# ATTiny13_TestBoard.net
KiCad netlist of a schematic drawn in EAGLE
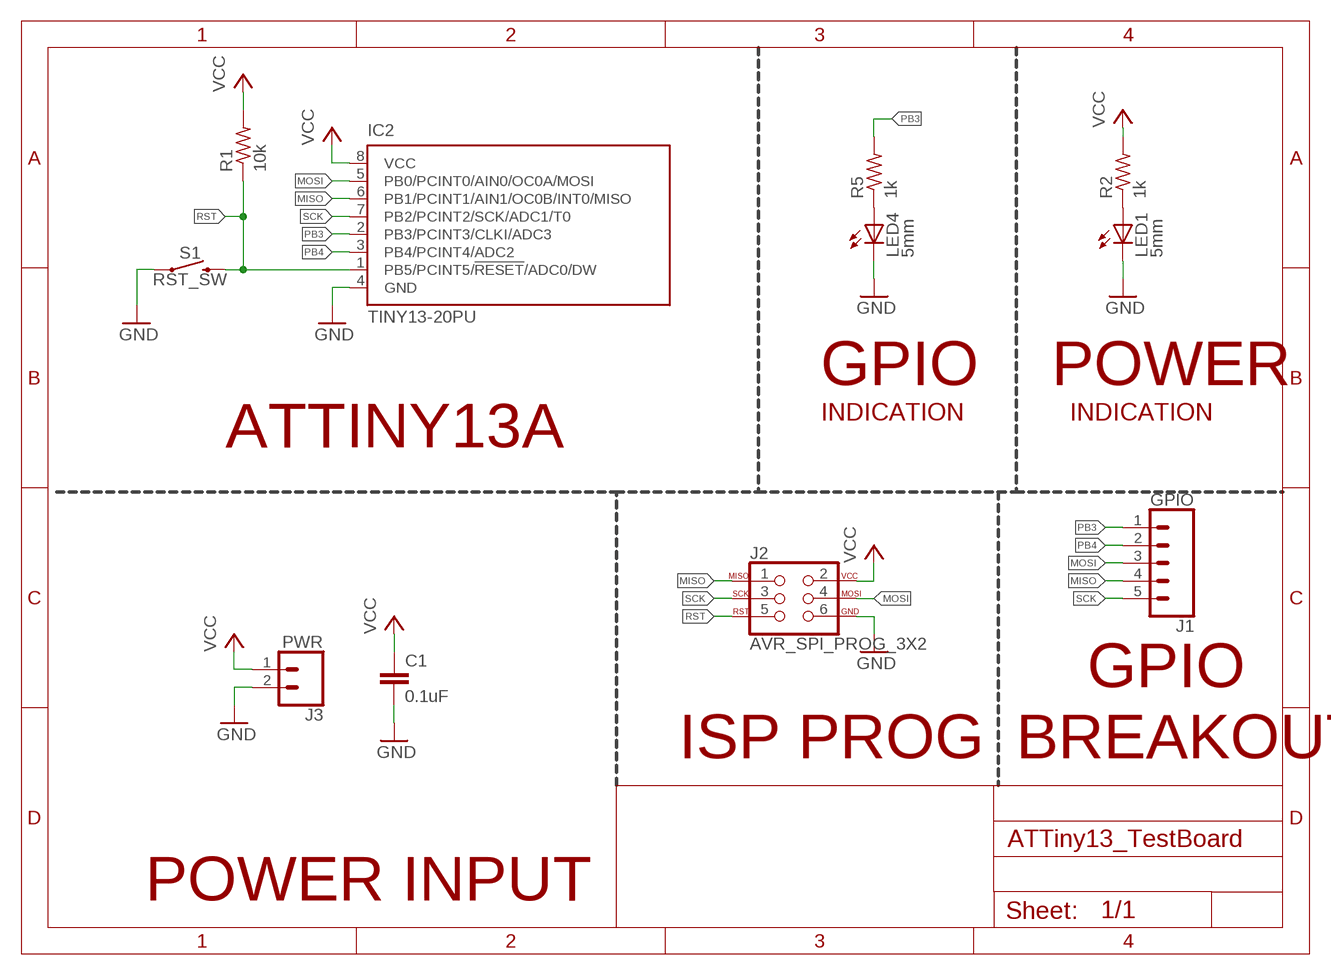
[diagram p0: schematic, sheet 1]

(export (version "E")
  (design (tool "Eeschema 10.0.6"))
  (components
    (comp (ref "C1")
      (value "0.1uF")
      (footprint "eagle-import:C050-025X075")
      (libsource (lib "eagle-import") (part "C-EU050-025X075"))
    )
    (comp (ref "IC2")
      (value "TINY13-20PU")
      (footprint "eagle-import:DIL08")
      (fields (field (name "MPN") "ATTINY13-20PU"))
      (libsource (lib "eagle-import") (part "TINY13PU-20"))
    )
    (comp (ref "J1")
      (value "GPIO")
      (footprint "eagle-import:SCREWTERMINAL-3.5MM-5")
      (libsource (lib "eagle-import") (part "CONN_05SCREW"))
    )
    (comp (ref "J2")
      (value "AVR_SPI_PROG_3X2")
      (footprint "eagle-import:2X3-NS")
      (libsource (lib "eagle-import") (part "AVR_SPI_PROG_3X2NS"))
    )
    (comp (ref "J3")
      (value "PWR")
      (footprint "eagle-import:SCREWTERMINAL-3.5MM-2-NS")
      (libsource (lib "eagle-import") (part "CONN_023.5MM-NO_SILK"))
    )
    (comp (ref "LED1")
      (value "5mm")
      (footprint "eagle-import:LED5MM")
      (libsource (lib "eagle-import") (part "LED5MM"))
    )
    (comp (ref "LED4")
      (value "5mm")
      (footprint "eagle-import:LED5MM")
      (libsource (lib "eagle-import") (part "LED5MM"))
    )
    (comp (ref "R1")
      (value "10k")
      (footprint "eagle-import:0204_7")
      (libsource (lib "eagle-import") (part "R-US_0204/7"))
    )
    (comp (ref "R2")
      (value "1k")
      (footprint "eagle-import:0204_7")
      (libsource (lib "eagle-import") (part "R-US_0204/7"))
    )
    (comp (ref "R5")
      (value "1k")
      (footprint "eagle-import:0204_7")
      (libsource (lib "eagle-import") (part "R-US_0204/7"))
    )
    (comp (ref "S1")
      (value "RST_SW")
      (footprint "eagle-import:TACTILE_SWITCH_PTH_6.0MM")
      (libsource (lib "eagle-import") (part "MOMENTARY-SWITCH-SPST-PTH-6.0MM"))
    )
  )
  (nets
    (net (code "1") (name "GND") (class "Default")
      (node (ref "C1") (pin "2") (pinfunction "2_2") (pintype "passive"))
      (node (ref "IC2") (pin "4") (pinfunction "GND_4") (pintype "power_in"))
      (node (ref "J2") (pin "6") (pinfunction "6_6") (pintype "passive"))
      (node (ref "J3") (pin "2") (pinfunction "2_2") (pintype "passive"))
      (node (ref "LED1") (pin "K") (pinfunction "C_K") (pintype "passive"))
      (node (ref "LED4") (pin "K") (pinfunction "C_K") (pintype "passive"))
      (node (ref "S1") (pin "1") (pinfunction "1_1") (pintype "passive"))
    )
    (net (code "2") (name "MISO") (class "Default")
      (node (ref "IC2") (pin "6") (pinfunction "PB1/PCINT1/AIN1/OC0B/INT0/MISO_6") (pintype "bidirectional"))
      (node (ref "J1") (pin "4") (pinfunction "4_4") (pintype "passive"))
      (node (ref "J2") (pin "1") (pinfunction "1_1") (pintype "passive"))
    )
    (net (code "3") (name "MOSI") (class "Default")
      (node (ref "IC2") (pin "5") (pinfunction "PB0/PCINT0/AIN0/OC0A/MOSI_5") (pintype "bidirectional"))
      (node (ref "J1") (pin "3") (pinfunction "3_3") (pintype "passive"))
      (node (ref "J2") (pin "4") (pinfunction "4_4") (pintype "passive"))
    )
    (net (code "4") (name "Net-(LED1-PadA)") (class "Default")
      (node (ref "LED1") (pin "A") (pinfunction "A_A") (pintype "passive"))
      (node (ref "R2") (pin "1") (pinfunction "1_1") (pintype "passive"))
    )
    (net (code "5") (name "Net-(LED4-PadA)") (class "Default")
      (node (ref "LED4") (pin "A") (pinfunction "A_A") (pintype "passive"))
      (node (ref "R5") (pin "1") (pinfunction "1_1") (pintype "passive"))
    )
    (net (code "6") (name "PB3") (class "Default")
      (node (ref "IC2") (pin "2") (pinfunction "PB3/PCINT3/CLKI/ADC3_2") (pintype "bidirectional"))
      (node (ref "J1") (pin "1") (pinfunction "1_1") (pintype "passive"))
      (node (ref "R5") (pin "2") (pinfunction "2_2") (pintype "passive"))
    )
    (net (code "7") (name "PB4") (class "Default")
      (node (ref "IC2") (pin "3") (pinfunction "PB4/PCINT4/ADC2_3") (pintype "bidirectional"))
      (node (ref "J1") (pin "2") (pinfunction "2_2") (pintype "passive"))
    )
    (net (code "8") (name "RST") (class "Default")
      (node (ref "IC2") (pin "1") (pinfunction "PB5/PCINT5/~{RESET}/ADC0/DW_1") (pintype "bidirectional"))
      (node (ref "J2") (pin "5") (pinfunction "5_5") (pintype "passive"))
      (node (ref "R1") (pin "1") (pinfunction "1_1") (pintype "passive"))
      (node (ref "S1") (pin "3") (pinfunction "2_3") (pintype "passive"))
    )
    (net (code "9") (name "SCK") (class "Default")
      (node (ref "IC2") (pin "7") (pinfunction "PB2/PCINT2/SCK/ADC1/T0_7") (pintype "bidirectional"))
      (node (ref "J1") (pin "5") (pinfunction "5_5") (pintype "passive"))
      (node (ref "J2") (pin "3") (pinfunction "3_3") (pintype "passive"))
    )
    (net (code "10") (name "VCC") (class "Default")
      (node (ref "C1") (pin "1") (pinfunction "1_1") (pintype "passive"))
      (node (ref "IC2") (pin "8") (pinfunction "VCC_8") (pintype "power_in"))
      (node (ref "J2") (pin "2") (pinfunction "2_2") (pintype "passive"))
      (node (ref "J3") (pin "1") (pinfunction "1_1") (pintype "passive"))
      (node (ref "R1") (pin "2") (pinfunction "2_2") (pintype "passive"))
      (node (ref "R2") (pin "2") (pinfunction "2_2") (pintype "passive"))
    )
  )
)
